# BespokeToast_Rev-0_v77.net
KiCad netlist of a schematic drawn in EAGLE
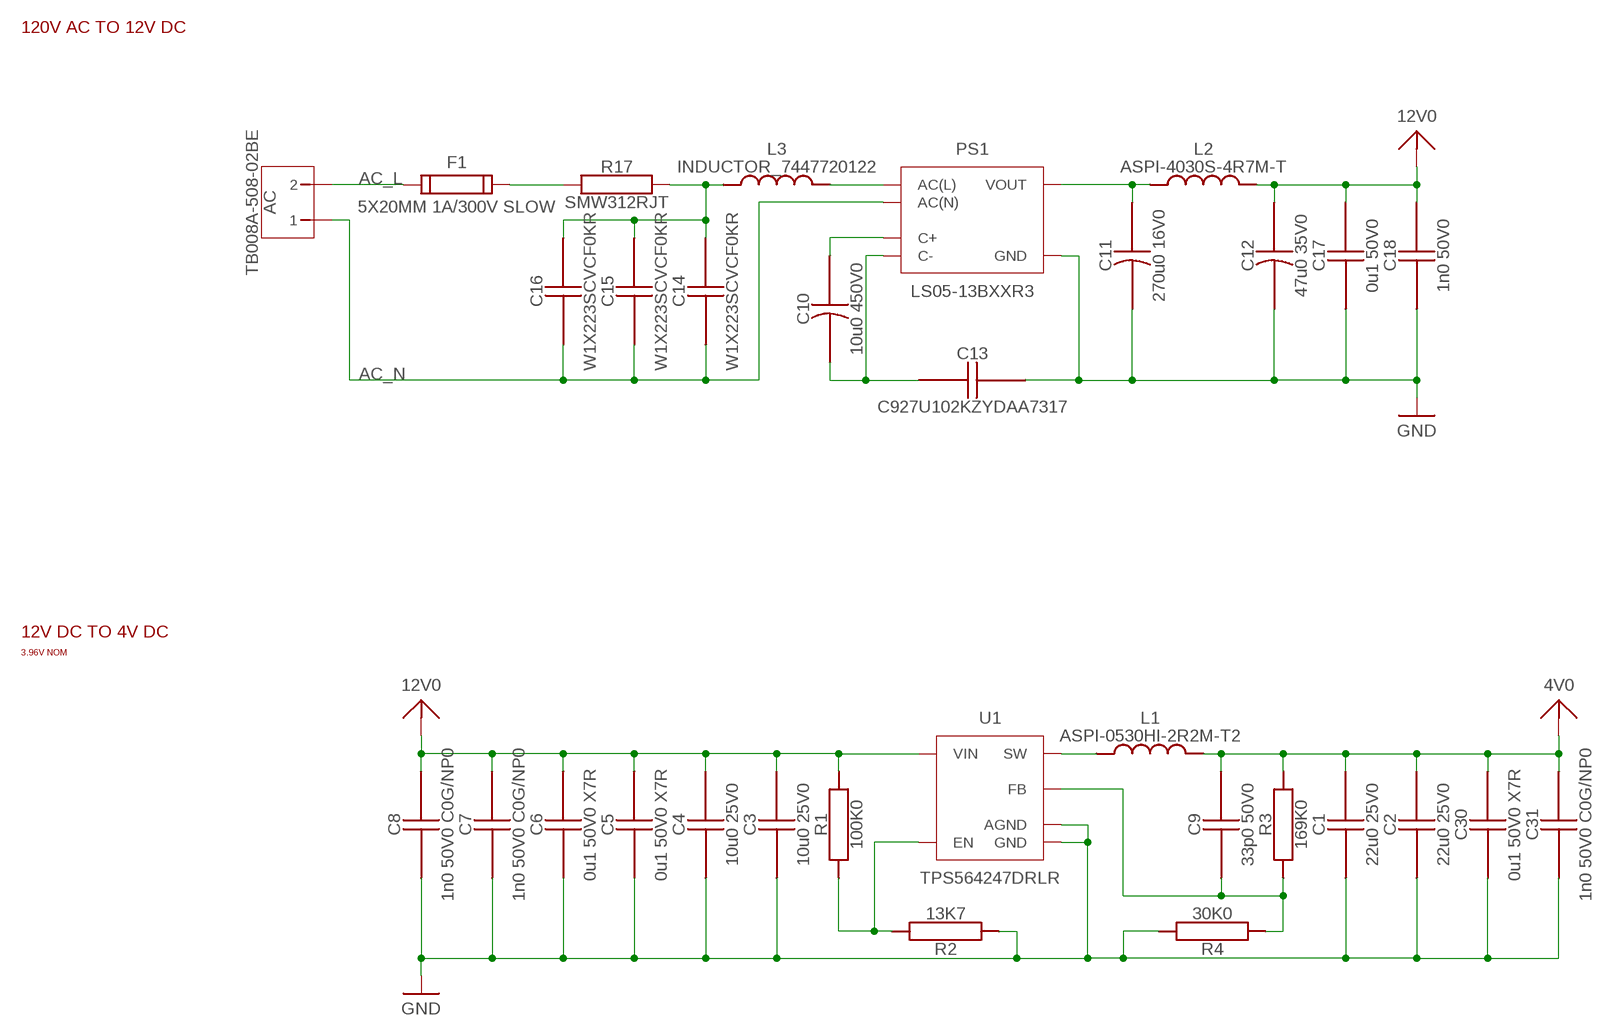
[diagram p0: schematic, sheet 1]
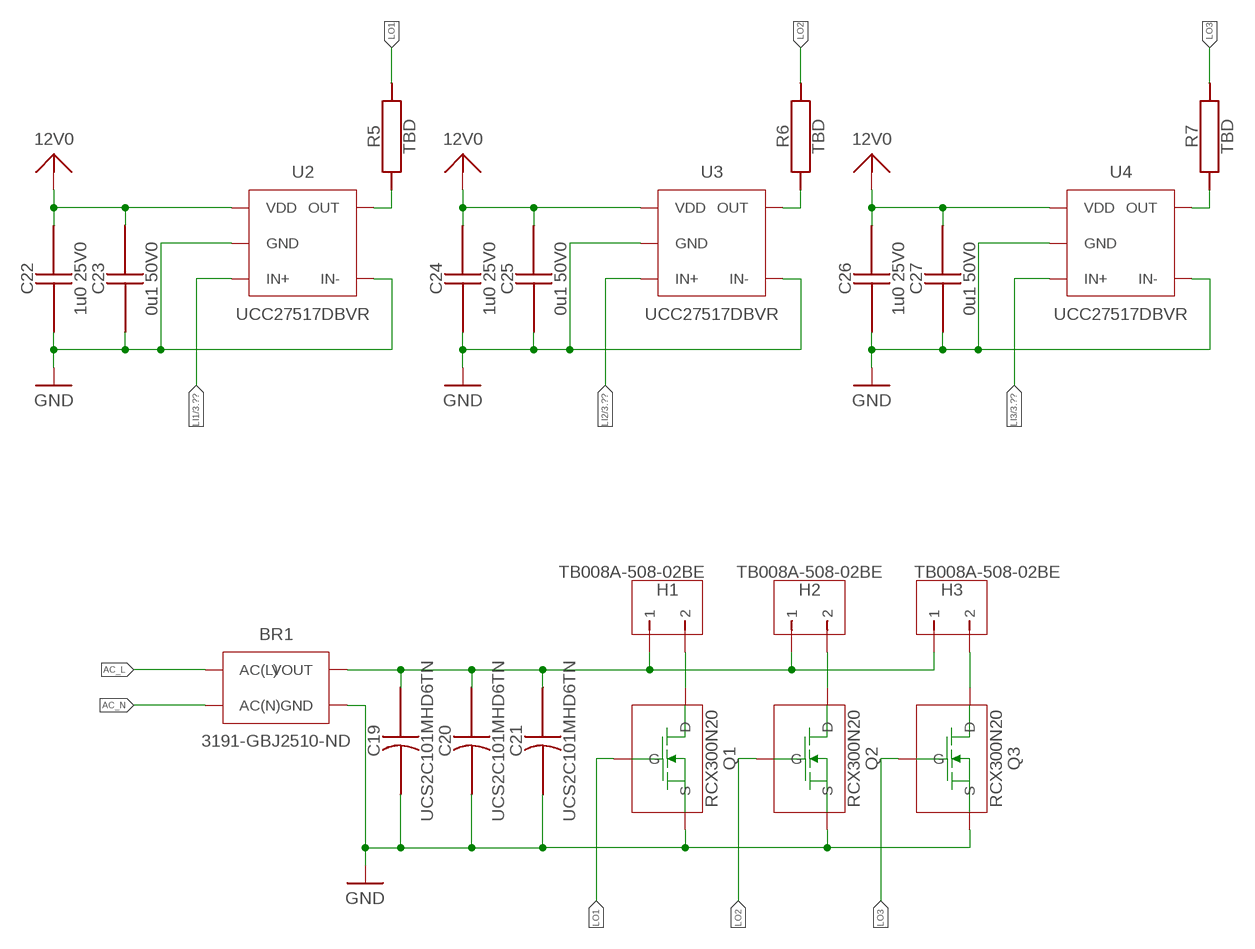
[diagram p1: schematic, sheet 2]
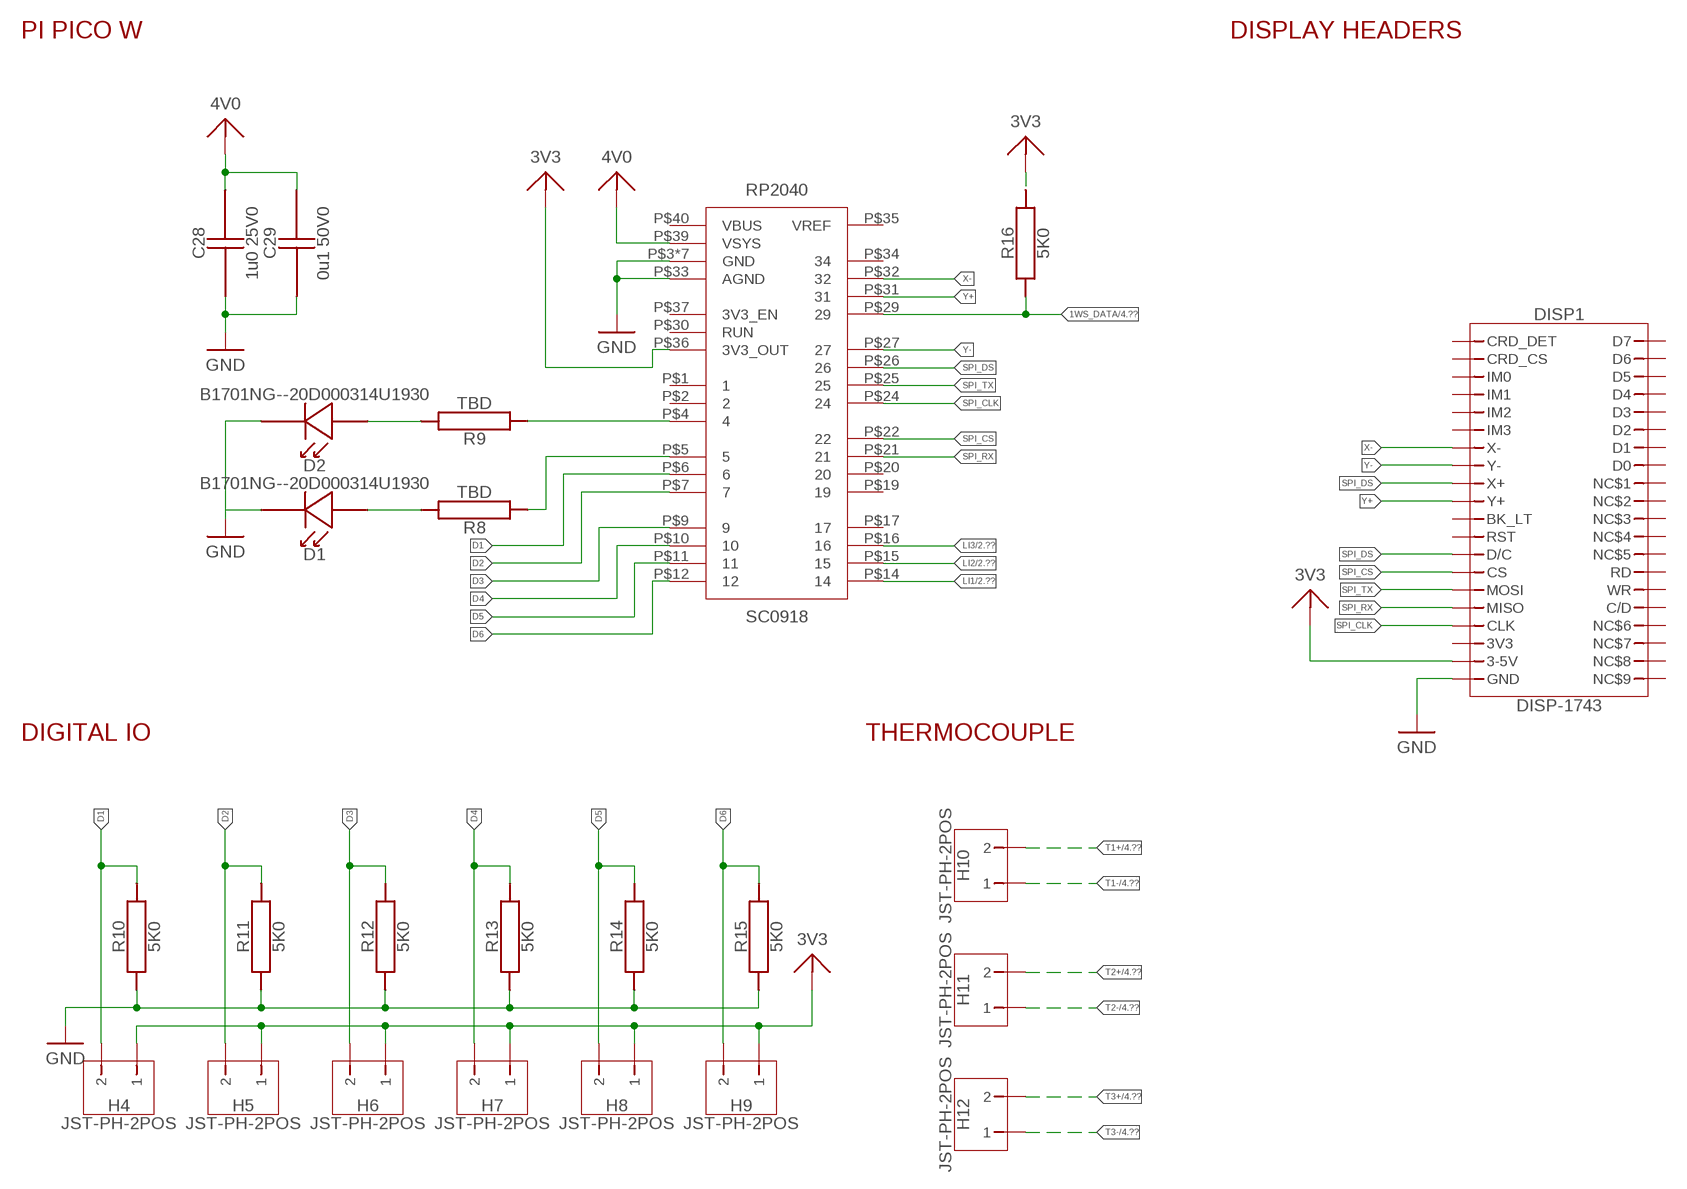
[diagram p2: schematic, sheet 3]
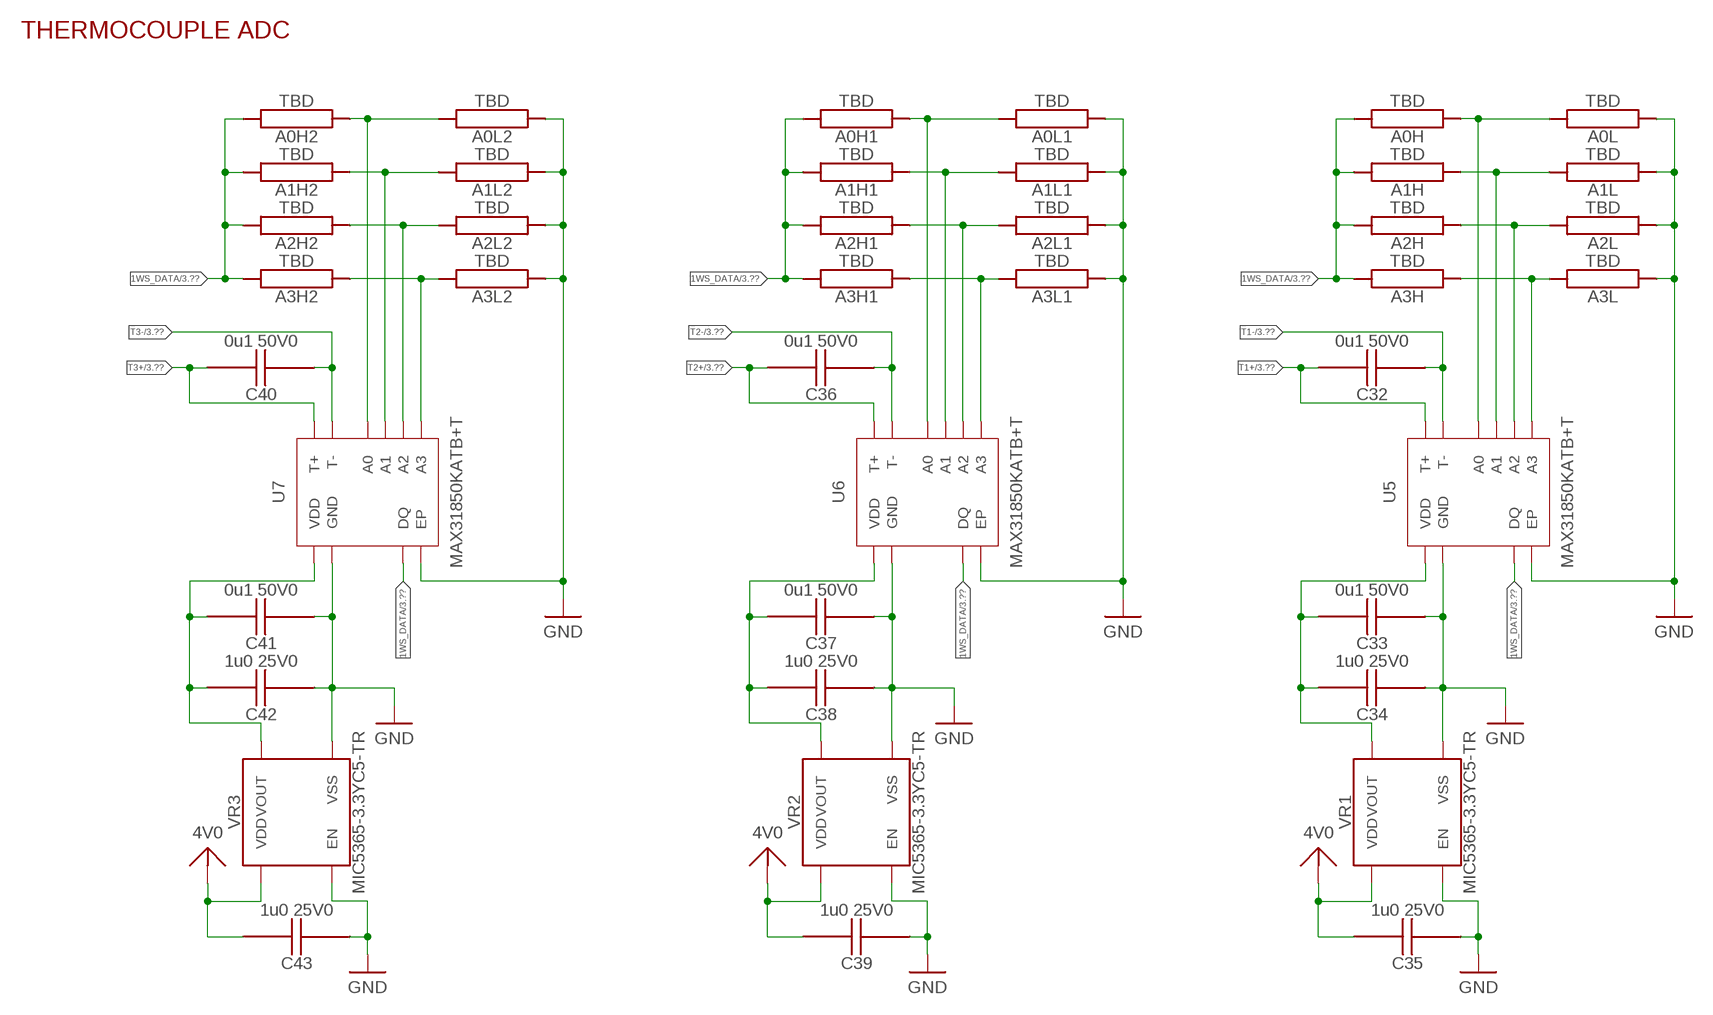
[diagram p3: schematic, sheet 4]

(export (version "E")
  (design (tool "Eeschema 10.0.6"))
  (components
    (comp (ref "BR1")
      (value "3191-GBJ2510-ND")
      (footprint "eagle-import:GBJ2510")
      (libsource (lib "eagle-import") (part "GBJ2510"))
    )
    (comp (ref "C19")
      (value "UCS2C101MHD6TN")
      (footprint "eagle-import:RUBYCON_CAP-POL-7.5X16")
      (libsource (lib "eagle-import") (part "CAP-POL_RUBYCON_CAP-POL-7.5X16"))
    )
    (comp (ref "C20")
      (value "UCS2C101MHD6TN")
      (footprint "eagle-import:RUBYCON_CAP-POL-7.5X16")
      (libsource (lib "eagle-import") (part "CAP-POL_RUBYCON_CAP-POL-7.5X16"))
    )
    (comp (ref "C21")
      (value "UCS2C101MHD6TN")
      (footprint "eagle-import:RUBYCON_CAP-POL-7.5X16")
      (libsource (lib "eagle-import") (part "CAP-POL_RUBYCON_CAP-POL-7.5X16"))
    )
    (comp (ref "C22")
      (value "1u0 25V0")
      (footprint "eagle-import:SAMSUNG_CAP-0805")
      (libsource (lib "eagle-import") (part "CAP-NON-POL_SAMSUNG-0805"))
    )
    (comp (ref "C23")
      (value "0u1 50V0")
      (footprint "eagle-import:SAMSUNG_CAP-0402")
      (libsource (lib "eagle-import") (part "CAP-NON-POL_SAMSUNG-0402"))
    )
    (comp (ref "C24")
      (value "1u0 25V0")
      (footprint "eagle-import:SAMSUNG_CAP-0805")
      (libsource (lib "eagle-import") (part "CAP-NON-POL_SAMSUNG-0805"))
    )
    (comp (ref "C25")
      (value "0u1 50V0")
      (footprint "eagle-import:SAMSUNG_CAP-0402")
      (libsource (lib "eagle-import") (part "CAP-NON-POL_SAMSUNG-0402"))
    )
    (comp (ref "C26")
      (value "1u0 25V0")
      (footprint "eagle-import:SAMSUNG_CAP-0805")
      (libsource (lib "eagle-import") (part "CAP-NON-POL_SAMSUNG-0805"))
    )
    (comp (ref "C27")
      (value "0u1 50V0")
      (footprint "eagle-import:SAMSUNG_CAP-0402")
      (libsource (lib "eagle-import") (part "CAP-NON-POL_SAMSUNG-0402"))
    )
    (comp (ref "H1")
      (value "TB008A-508-02BE")
      (footprint "eagle-import:TB008A-508-02BE")
      (libsource (lib "eagle-import") (part "TB008A-508-02BE"))
    )
    (comp (ref "H2")
      (value "TB008A-508-02BE")
      (footprint "eagle-import:TB008A-508-02BE")
      (libsource (lib "eagle-import") (part "TB008A-508-02BE"))
    )
    (comp (ref "H3")
      (value "TB008A-508-02BE")
      (footprint "eagle-import:TB008A-508-02BE")
      (libsource (lib "eagle-import") (part "TB008A-508-02BE"))
    )
    (comp (ref "Q1")
      (value "RCX300N20")
      (footprint "eagle-import:FET_TO220-VTH")
      (libsource (lib "eagle-import") (part "FET-NCH_FET_TO220-VTH"))
    )
    (comp (ref "Q2")
      (value "RCX300N20")
      (footprint "eagle-import:FET_TO220-VTH")
      (libsource (lib "eagle-import") (part "FET-NCH_FET_TO220-VTH"))
    )
    (comp (ref "Q3")
      (value "RCX300N20")
      (footprint "eagle-import:FET_TO220-VTH")
      (libsource (lib "eagle-import") (part "FET-NCH_FET_TO220-VTH"))
    )
    (comp (ref "R5")
      (value "TBD")
      (footprint "eagle-import:YAGEO_RES-0402")
      (libsource (lib "eagle-import") (part "RES-CHIP_YAGEO-0402"))
    )
    (comp (ref "R6")
      (value "TBD")
      (footprint "eagle-import:YAGEO_RES-0402")
      (libsource (lib "eagle-import") (part "RES-CHIP_YAGEO-0402"))
    )
    (comp (ref "R7")
      (value "TBD")
      (footprint "eagle-import:YAGEO_RES-0402")
      (libsource (lib "eagle-import") (part "RES-CHIP_YAGEO-0402"))
    )
    (comp (ref "U2")
      (value "UCC27517DBVR")
      (footprint "eagle-import:UCC27517DBVR")
      (libsource (lib "eagle-import") (part "UCC27517DBVR"))
    )
    (comp (ref "U3")
      (value "UCC27517DBVR")
      (footprint "eagle-import:UCC27517DBVR")
      (libsource (lib "eagle-import") (part "UCC27517DBVR"))
    )
    (comp (ref "U4")
      (value "UCC27517DBVR")
      (footprint "eagle-import:UCC27517DBVR")
      (libsource (lib "eagle-import") (part "UCC27517DBVR"))
    )
    (comp (ref "C28")
      (value "1u0 25V0")
      (footprint "eagle-import:SAMSUNG_CAP-0805")
      (libsource (lib "eagle-import") (part "CAP-NON-POL_SAMSUNG-0805"))
    )
    (comp (ref "C29")
      (value "0u1 50V0")
      (footprint "eagle-import:SAMSUNG_CAP-0402")
      (libsource (lib "eagle-import") (part "CAP-NON-POL_SAMSUNG-0402"))
    )
    (comp (ref "D1")
      (value "B1701NG--20D000314U1930")
      (footprint "eagle-import:B1701NG--20D000314U1930")
      (libsource (lib "eagle-import") (part "DIODE-LED_B1701NG--20D000314U1930"))
    )
    (comp (ref "D2")
      (value "B1701NG--20D000314U1930")
      (footprint "eagle-import:B1701NG--20D000314U1930")
      (libsource (lib "eagle-import") (part "DIODE-LED_B1701NG--20D000314U1930"))
    )
    (comp (ref "DISP1")
      (value "DISP-1743")
      (footprint "eagle-import:DISP-1743")
      (libsource (lib "eagle-import") (part "DISP-1743"))
    )
    (comp (ref "H4")
      (value "JST-PH-2POS")
      (footprint "eagle-import:JST-PH-2POS")
      (libsource (lib "eagle-import") (part "JST-PH-2POS"))
    )
    (comp (ref "H5")
      (value "JST-PH-2POS")
      (footprint "eagle-import:JST-PH-2POS")
      (libsource (lib "eagle-import") (part "JST-PH-2POS"))
    )
    (comp (ref "H6")
      (value "JST-PH-2POS")
      (footprint "eagle-import:JST-PH-2POS")
      (libsource (lib "eagle-import") (part "JST-PH-2POS"))
    )
    (comp (ref "H7")
      (value "JST-PH-2POS")
      (footprint "eagle-import:JST-PH-2POS")
      (libsource (lib "eagle-import") (part "JST-PH-2POS"))
    )
    (comp (ref "H8")
      (value "JST-PH-2POS")
      (footprint "eagle-import:JST-PH-2POS")
      (libsource (lib "eagle-import") (part "JST-PH-2POS"))
    )
    (comp (ref "H9")
      (value "JST-PH-2POS")
      (footprint "eagle-import:JST-PH-2POS")
      (libsource (lib "eagle-import") (part "JST-PH-2POS"))
    )
    (comp (ref "H10")
      (value "JST-PH-2POS")
      (footprint "eagle-import:JST-PH-2POS")
      (libsource (lib "eagle-import") (part "JST-PH-2POS"))
    )
    (comp (ref "H11")
      (value "JST-PH-2POS")
      (footprint "eagle-import:JST-PH-2POS")
      (libsource (lib "eagle-import") (part "JST-PH-2POS"))
    )
    (comp (ref "H12")
      (value "JST-PH-2POS")
      (footprint "eagle-import:JST-PH-2POS")
      (libsource (lib "eagle-import") (part "JST-PH-2POS"))
    )
    (comp (ref "R8")
      (value "TBD")
      (footprint "eagle-import:YAGEO_RES-0402")
      (libsource (lib "eagle-import") (part "RES-CHIP_YAGEO-0402"))
    )
    (comp (ref "R9")
      (value "TBD")
      (footprint "eagle-import:YAGEO_RES-0402")
      (libsource (lib "eagle-import") (part "RES-CHIP_YAGEO-0402"))
    )
    (comp (ref "R10")
      (value "5K0")
      (footprint "eagle-import:YAGEO_RES-0402")
      (libsource (lib "eagle-import") (part "RES-CHIP_YAGEO-0402"))
    )
    (comp (ref "R11")
      (value "5K0")
      (footprint "eagle-import:YAGEO_RES-0402")
      (libsource (lib "eagle-import") (part "RES-CHIP_YAGEO-0402"))
    )
    (comp (ref "R12")
      (value "5K0")
      (footprint "eagle-import:YAGEO_RES-0402")
      (libsource (lib "eagle-import") (part "RES-CHIP_YAGEO-0402"))
    )
    (comp (ref "R13")
      (value "5K0")
      (footprint "eagle-import:YAGEO_RES-0402")
      (libsource (lib "eagle-import") (part "RES-CHIP_YAGEO-0402"))
    )
    (comp (ref "R14")
      (value "5K0")
      (footprint "eagle-import:YAGEO_RES-0402")
      (libsource (lib "eagle-import") (part "RES-CHIP_YAGEO-0402"))
    )
    (comp (ref "R15")
      (value "5K0")
      (footprint "eagle-import:YAGEO_RES-0402")
      (libsource (lib "eagle-import") (part "RES-CHIP_YAGEO-0402"))
    )
    (comp (ref "R16")
      (value "5K0")
      (footprint "eagle-import:YAGEO_RES-0402")
      (libsource (lib "eagle-import") (part "RES-CHIP_YAGEO-0402"))
    )
    (comp (ref "RP2040")
      (value "SC0918")
      (footprint "eagle-import:SC0915")
      (libsource (lib "eagle-import") (part "SC0915"))
    )
    (comp (ref "A0H")
      (value "TBD")
      (footprint "eagle-import:YAGEO_RES-0402")
      (fields (field (name "SPICEPREFIX") "B"))
      (libsource (lib "eagle-import") (part "RES-CHIP_YAGEO-0402"))
    )
    (comp (ref "A0H1")
      (value "TBD")
      (footprint "eagle-import:YAGEO_RES-0402")
      (fields (field (name "SPICEPREFIX") "B"))
      (libsource (lib "eagle-import") (part "RES-CHIP_YAGEO-0402"))
    )
    (comp (ref "A0H2")
      (value "TBD")
      (footprint "eagle-import:YAGEO_RES-0402")
      (fields (field (name "SPICEPREFIX") "B"))
      (libsource (lib "eagle-import") (part "RES-CHIP_YAGEO-0402"))
    )
    (comp (ref "A0L")
      (value "TBD")
      (footprint "eagle-import:YAGEO_RES-0402")
      (fields (field (name "SPICEPREFIX") "B"))
      (libsource (lib "eagle-import") (part "RES-CHIP_YAGEO-0402"))
    )
    (comp (ref "A0L1")
      (value "TBD")
      (footprint "eagle-import:YAGEO_RES-0402")
      (fields (field (name "SPICEPREFIX") "B"))
      (libsource (lib "eagle-import") (part "RES-CHIP_YAGEO-0402"))
    )
    (comp (ref "A0L2")
      (value "TBD")
      (footprint "eagle-import:YAGEO_RES-0402")
      (fields (field (name "SPICEPREFIX") "B"))
      (libsource (lib "eagle-import") (part "RES-CHIP_YAGEO-0402"))
    )
    (comp (ref "A1H")
      (value "TBD")
      (footprint "eagle-import:YAGEO_RES-0402")
      (fields (field (name "SPICEPREFIX") "B"))
      (libsource (lib "eagle-import") (part "RES-CHIP_YAGEO-0402"))
    )
    (comp (ref "A1H1")
      (value "TBD")
      (footprint "eagle-import:YAGEO_RES-0402")
      (fields (field (name "SPICEPREFIX") "B"))
      (libsource (lib "eagle-import") (part "RES-CHIP_YAGEO-0402"))
    )
    (comp (ref "A1H2")
      (value "TBD")
      (footprint "eagle-import:YAGEO_RES-0402")
      (fields (field (name "SPICEPREFIX") "B"))
      (libsource (lib "eagle-import") (part "RES-CHIP_YAGEO-0402"))
    )
    (comp (ref "A1L")
      (value "TBD")
      (footprint "eagle-import:YAGEO_RES-0402")
      (fields (field (name "SPICEPREFIX") "B"))
      (libsource (lib "eagle-import") (part "RES-CHIP_YAGEO-0402"))
    )
    (comp (ref "A1L1")
      (value "TBD")
      (footprint "eagle-import:YAGEO_RES-0402")
      (fields (field (name "SPICEPREFIX") "B"))
      (libsource (lib "eagle-import") (part "RES-CHIP_YAGEO-0402"))
    )
    (comp (ref "A1L2")
      (value "TBD")
      (footprint "eagle-import:YAGEO_RES-0402")
      (fields (field (name "SPICEPREFIX") "B"))
      (libsource (lib "eagle-import") (part "RES-CHIP_YAGEO-0402"))
    )
    (comp (ref "A2H")
      (value "TBD")
      (footprint "eagle-import:YAGEO_RES-0402")
      (fields (field (name "SPICEPREFIX") "B"))
      (libsource (lib "eagle-import") (part "RES-CHIP_YAGEO-0402"))
    )
    (comp (ref "A2H1")
      (value "TBD")
      (footprint "eagle-import:YAGEO_RES-0402")
      (fields (field (name "SPICEPREFIX") "B"))
      (libsource (lib "eagle-import") (part "RES-CHIP_YAGEO-0402"))
    )
    (comp (ref "A2H2")
      (value "TBD")
      (footprint "eagle-import:YAGEO_RES-0402")
      (fields (field (name "SPICEPREFIX") "B"))
      (libsource (lib "eagle-import") (part "RES-CHIP_YAGEO-0402"))
    )
    (comp (ref "A2L")
      (value "TBD")
      (footprint "eagle-import:YAGEO_RES-0402")
      (fields (field (name "SPICEPREFIX") "B"))
      (libsource (lib "eagle-import") (part "RES-CHIP_YAGEO-0402"))
    )
    (comp (ref "A2L1")
      (value "TBD")
      (footprint "eagle-import:YAGEO_RES-0402")
      (fields (field (name "SPICEPREFIX") "B"))
      (libsource (lib "eagle-import") (part "RES-CHIP_YAGEO-0402"))
    )
    (comp (ref "A2L2")
      (value "TBD")
      (footprint "eagle-import:YAGEO_RES-0402")
      (fields (field (name "SPICEPREFIX") "B"))
      (libsource (lib "eagle-import") (part "RES-CHIP_YAGEO-0402"))
    )
    (comp (ref "A3H")
      (value "TBD")
      (footprint "eagle-import:YAGEO_RES-0402")
      (fields (field (name "SPICEPREFIX") "B"))
      (libsource (lib "eagle-import") (part "RES-CHIP_YAGEO-0402"))
    )
    (comp (ref "A3H1")
      (value "TBD")
      (footprint "eagle-import:YAGEO_RES-0402")
      (fields (field (name "SPICEPREFIX") "B"))
      (libsource (lib "eagle-import") (part "RES-CHIP_YAGEO-0402"))
    )
    (comp (ref "A3H2")
      (value "TBD")
      (footprint "eagle-import:YAGEO_RES-0402")
      (fields (field (name "SPICEPREFIX") "B"))
      (libsource (lib "eagle-import") (part "RES-CHIP_YAGEO-0402"))
    )
    (comp (ref "A3L")
      (value "TBD")
      (footprint "eagle-import:YAGEO_RES-0402")
      (fields (field (name "SPICEPREFIX") "B"))
      (libsource (lib "eagle-import") (part "RES-CHIP_YAGEO-0402"))
    )
    (comp (ref "A3L1")
      (value "TBD")
      (footprint "eagle-import:YAGEO_RES-0402")
      (fields (field (name "SPICEPREFIX") "B"))
      (libsource (lib "eagle-import") (part "RES-CHIP_YAGEO-0402"))
    )
    (comp (ref "A3L2")
      (value "TBD")
      (footprint "eagle-import:YAGEO_RES-0402")
      (fields (field (name "SPICEPREFIX") "B"))
      (libsource (lib "eagle-import") (part "RES-CHIP_YAGEO-0402"))
    )
    (comp (ref "C32")
      (value "0u1 50V0")
      (footprint "eagle-import:SAMSUNG_CAP-0402")
      (fields (field (name "SPICEPREFIX") "C"))
      (libsource (lib "eagle-import") (part "CAP-NON-POL_SAMSUNG-0402"))
    )
    (comp (ref "C33")
      (value "0u1 50V0")
      (footprint "eagle-import:SAMSUNG_CAP-0402")
      (fields (field (name "SPICEPREFIX") "C"))
      (libsource (lib "eagle-import") (part "CAP-NON-POL_SAMSUNG-0402"))
    )
    (comp (ref "C34")
      (value "1u0 25V0")
      (footprint "eagle-import:SAMSUNG_CAP-0603")
      (fields (field (name "SPICEPREFIX") "C"))
      (libsource (lib "eagle-import") (part "CAP-NON-POL_SAMSUNG-0603"))
    )
    (comp (ref "C35")
      (value "1u0 25V0")
      (footprint "eagle-import:SAMSUNG_CAP-0603")
      (fields (field (name "SPICEPREFIX") "C"))
      (libsource (lib "eagle-import") (part "CAP-NON-POL_SAMSUNG-0603"))
    )
    (comp (ref "C36")
      (value "0u1 50V0")
      (footprint "eagle-import:SAMSUNG_CAP-0402")
      (fields (field (name "SPICEPREFIX") "C"))
      (libsource (lib "eagle-import") (part "CAP-NON-POL_SAMSUNG-0402"))
    )
    (comp (ref "C37")
      (value "0u1 50V0")
      (footprint "eagle-import:SAMSUNG_CAP-0402")
      (fields (field (name "SPICEPREFIX") "C"))
      (libsource (lib "eagle-import") (part "CAP-NON-POL_SAMSUNG-0402"))
    )
    (comp (ref "C38")
      (value "1u0 25V0")
      (footprint "eagle-import:SAMSUNG_CAP-0603")
      (fields (field (name "SPICEPREFIX") "C"))
      (libsource (lib "eagle-import") (part "CAP-NON-POL_SAMSUNG-0603"))
    )
    (comp (ref "C39")
      (value "1u0 25V0")
      (footprint "eagle-import:SAMSUNG_CAP-0603")
      (fields (field (name "SPICEPREFIX") "C"))
      (libsource (lib "eagle-import") (part "CAP-NON-POL_SAMSUNG-0603"))
    )
    (comp (ref "C40")
      (value "0u1 50V0")
      (footprint "eagle-import:SAMSUNG_CAP-0402")
      (fields (field (name "SPICEPREFIX") "C"))
      (libsource (lib "eagle-import") (part "CAP-NON-POL_SAMSUNG-0402"))
    )
    (comp (ref "C41")
      (value "0u1 50V0")
      (footprint "eagle-import:SAMSUNG_CAP-0402")
      (fields (field (name "SPICEPREFIX") "C"))
      (libsource (lib "eagle-import") (part "CAP-NON-POL_SAMSUNG-0402"))
    )
    (comp (ref "C42")
      (value "1u0 25V0")
      (footprint "eagle-import:SAMSUNG_CAP-0603")
      (fields (field (name "SPICEPREFIX") "C"))
      (libsource (lib "eagle-import") (part "CAP-NON-POL_SAMSUNG-0603"))
    )
    (comp (ref "C43")
      (value "1u0 25V0")
      (footprint "eagle-import:SAMSUNG_CAP-0603")
      (fields (field (name "SPICEPREFIX") "C"))
      (libsource (lib "eagle-import") (part "CAP-NON-POL_SAMSUNG-0603"))
    )
    (comp (ref "U5")
      (value "MAX31850KATB+T")
      (footprint "eagle-import:MAX31850")
      (fields (field (name "SPICEPREFIX") "X"))
      (libsource (lib "eagle-import") (part "MAX31850_MAX31850KATB+T"))
    )
    (comp (ref "U6")
      (value "MAX31850KATB+T")
      (footprint "eagle-import:MAX31850")
      (fields (field (name "SPICEPREFIX") "X"))
      (libsource (lib "eagle-import") (part "MAX31850_MAX31850KATB+T"))
    )
    (comp (ref "U7")
      (value "MAX31850KATB+T")
      (footprint "eagle-import:MAX31850")
      (fields (field (name "SPICEPREFIX") "X"))
      (libsource (lib "eagle-import") (part "MAX31850_MAX31850KATB+T"))
    )
    (comp (ref "VR1")
      (value "MIC5365-3.3YC5-TR")
      (footprint "eagle-import:MIC5365-3.3YC5-TR")
      (fields (field (name "SPICEPREFIX") "E"))
      (libsource (lib "eagle-import") (part "MIC5365-3.3YC5-TR{dblquote}"))
    )
    (comp (ref "VR2")
      (value "MIC5365-3.3YC5-TR")
      (footprint "eagle-import:MIC5365-3.3YC5-TR")
      (fields (field (name "SPICEPREFIX") "E"))
      (libsource (lib "eagle-import") (part "MIC5365-3.3YC5-TR{dblquote}"))
    )
    (comp (ref "VR3")
      (value "MIC5365-3.3YC5-TR")
      (footprint "eagle-import:MIC5365-3.3YC5-TR")
      (fields (field (name "SPICEPREFIX") "E"))
      (libsource (lib "eagle-import") (part "MIC5365-3.3YC5-TR{dblquote}"))
    )
    (comp (ref "AC")
      (value "TB008A-508-02BE")
      (footprint "eagle-import:TB008A-508-02BE")
      (libsource (lib "eagle-import") (part "TB008A-508-02BE"))
    )
    (comp (ref "C1")
      (value "22u0 25V0")
      (footprint "eagle-import:SAMSUNG_CAP-0805")
      (libsource (lib "eagle-import") (part "CAP-NON-POL_SAMSUNG-0805"))
    )
    (comp (ref "C2")
      (value "22u0 25V0")
      (footprint "eagle-import:SAMSUNG_CAP-0805")
      (libsource (lib "eagle-import") (part "CAP-NON-POL_SAMSUNG-0805"))
    )
    (comp (ref "C3")
      (value "10u0 25V0")
      (footprint "eagle-import:SAMSUNG_CAP-0805")
      (libsource (lib "eagle-import") (part "CAP-NON-POL_SAMSUNG-0805"))
    )
    (comp (ref "C4")
      (value "10u0 25V0")
      (footprint "eagle-import:SAMSUNG_CAP-0805")
      (libsource (lib "eagle-import") (part "CAP-NON-POL_SAMSUNG-0805"))
    )
    (comp (ref "C5")
      (value "0u1 50V0 X7R")
      (footprint "eagle-import:SAMSUNG_CAP-0402")
      (libsource (lib "eagle-import") (part "CAP-NON-POL_SAMSUNG-0402"))
    )
    (comp (ref "C6")
      (value "0u1 50V0 X7R")
      (footprint "eagle-import:SAMSUNG_CAP-0402")
      (libsource (lib "eagle-import") (part "CAP-NON-POL_SAMSUNG-0402"))
    )
    (comp (ref "C7")
      (value "1n0 50V0 C0G/NP0")
      (footprint "eagle-import:SAMSUNG_CAP-0402")
      (libsource (lib "eagle-import") (part "CAP-NON-POL_SAMSUNG-0402"))
    )
    (comp (ref "C8")
      (value "1n0 50V0 C0G/NP0")
      (footprint "eagle-import:SAMSUNG_CAP-0402")
      (libsource (lib "eagle-import") (part "CAP-NON-POL_SAMSUNG-0402"))
    )
    (comp (ref "C9")
      (value "33p0 50V0")
      (footprint "eagle-import:SAMSUNG_CAP-0402")
      (libsource (lib "eagle-import") (part "CAP-NON-POL_SAMSUNG-0402"))
    )
    (comp (ref "C10")
      (value "10u0 450V0")
      (footprint "eagle-import:RUBYCON_CAP-POL-5X10")
      (libsource (lib "eagle-import") (part "CAP-POL_RUBYCON_CAP-POL-5X10"))
    )
    (comp (ref "C11")
      (value "270u0 16V0")
      (footprint "eagle-import:RUBYCON_CAP-POL-3.5X8")
      (libsource (lib "eagle-import") (part "CAP-POL_RUBYCON_CAP-POL-3.5X8"))
    )
    (comp (ref "C12")
      (value "47u0 35V0")
      (footprint "eagle-import:RUBYCON_CAP-POL-3.5X8")
      (libsource (lib "eagle-import") (part "CAP-POL_RUBYCON_CAP-POL-3.5X8"))
    )
    (comp (ref "C13")
      (value "C927U102KZYDAA7317")
      (footprint "eagle-import:TH_CAP-7.5")
      (libsource (lib "eagle-import") (part "CAP-NON-POL_TC_CAP-7.5"))
    )
    (comp (ref "C14")
      (value "W1X223SCVCF0KR")
      (footprint "eagle-import:TH_CAP-7.5")
      (libsource (lib "eagle-import") (part "CAP-NON-POL_TC_CAP-7.5"))
    )
    (comp (ref "C15")
      (value "W1X223SCVCF0KR")
      (footprint "eagle-import:TH_CAP-7.5")
      (libsource (lib "eagle-import") (part "CAP-NON-POL_TC_CAP-7.5"))
    )
    (comp (ref "C16")
      (value "W1X223SCVCF0KR")
      (footprint "eagle-import:TH_CAP-7.5")
      (libsource (lib "eagle-import") (part "CAP-NON-POL_TC_CAP-7.5"))
    )
    (comp (ref "C17")
      (value "0u1 50V0")
      (footprint "eagle-import:SAMSUNG_CAP-0402")
      (libsource (lib "eagle-import") (part "CAP-NON-POL_SAMSUNG-0402"))
    )
    (comp (ref "C18")
      (value "1n0 50V0")
      (footprint "eagle-import:SAMSUNG_CAP-0402")
      (libsource (lib "eagle-import") (part "CAP-NON-POL_SAMSUNG-0402"))
    )
    (comp (ref "C30")
      (value "0u1 50V0 X7R")
      (footprint "eagle-import:SAMSUNG_CAP-0402")
      (libsource (lib "eagle-import") (part "CAP-NON-POL_SAMSUNG-0402"))
    )
    (comp (ref "C31")
      (value "1n0 50V0 C0G/NP0")
      (footprint "eagle-import:SAMSUNG_CAP-0402")
      (libsource (lib "eagle-import") (part "CAP-NON-POL_SAMSUNG-0402"))
    )
    (comp (ref "F1")
      (value "5X20MM 1A/300V SLOW")
      (footprint "eagle-import:FC-203-22")
      (libsource (lib "eagle-import") (part "FUSE_FC-203-22-5X20MM"))
    )
    (comp (ref "L1")
      (value "ASPI-0530HI-2R2M-T2")
      (footprint "eagle-import:ASPI-0530HI-2R2M-T2")
      (libsource (lib "eagle-import") (part "INDUCTOR_ASPI-0530HI-2R2M-T2"))
    )
    (comp (ref "L2")
      (value "ASPI-4030S-4R7M-T")
      (footprint "eagle-import:ASPI-4030S-4R7M-T")
      (libsource (lib "eagle-import") (part "INDUCTOR_ASPI-4030S-4R7M-T"))
    )
    (comp (ref "L3")
      (value "INDUCTOR_7447720122")
      (footprint "eagle-import:7447720122")
      (libsource (lib "eagle-import") (part "INDUCTOR_7447720122"))
    )
    (comp (ref "PS1")
      (value "LS05-13BXXR3")
      (footprint "eagle-import:LS05-13BXXR3")
      (libsource (lib "eagle-import") (part "LS05-13BXXR3"))
    )
    (comp (ref "R1")
      (value "100K0")
      (footprint "eagle-import:YAGEO_RES-0402")
      (libsource (lib "eagle-import") (part "RES-CHIP_YAGEO-0402"))
    )
    (comp (ref "R2")
      (value "13K7")
      (footprint "eagle-import:YAGEO_RES-0402")
      (libsource (lib "eagle-import") (part "RES-CHIP_YAGEO-0402"))
    )
    (comp (ref "R3")
      (value "169K0")
      (footprint "eagle-import:YAGEO_RES-0402")
      (libsource (lib "eagle-import") (part "RES-CHIP_YAGEO-0402"))
    )
    (comp (ref "R4")
      (value "30K0")
      (footprint "eagle-import:YAGEO_RES-0402")
      (libsource (lib "eagle-import") (part "RES-CHIP_YAGEO-0402"))
    )
    (comp (ref "R17")
      (value "SMW312RJT")
      (footprint "eagle-import:SMW312RJT")
      (libsource (lib "eagle-import") (part "SMW312RJT"))
    )
    (comp (ref "U1")
      (value "TPS564247DRLR")
      (footprint "eagle-import:TPS564247DRLR")
      (libsource (lib "eagle-import") (part "TPS564247DRLR"))
    )
  )
  (nets
    (net (code "1") (name "1WS_DATA") (class "Default")
      (node (ref "A0H") (pin "P$2") (pinfunction "P$2_P$2") (pintype "bidirectional"))
      (node (ref "A0H1") (pin "P$2") (pinfunction "P$2_P$2") (pintype "bidirectional"))
      (node (ref "A0H2") (pin "P$2") (pinfunction "P$2_P$2") (pintype "bidirectional"))
      (node (ref "A1H") (pin "P$2") (pinfunction "P$2_P$2") (pintype "bidirectional"))
      (node (ref "A1H1") (pin "P$2") (pinfunction "P$2_P$2") (pintype "bidirectional"))
      (node (ref "A1H2") (pin "P$2") (pinfunction "P$2_P$2") (pintype "bidirectional"))
      (node (ref "A2H") (pin "P$2") (pinfunction "P$2_P$2") (pintype "bidirectional"))
      (node (ref "A2H1") (pin "P$2") (pinfunction "P$2_P$2") (pintype "bidirectional"))
      (node (ref "A2H2") (pin "P$2") (pinfunction "P$2_P$2") (pintype "bidirectional"))
      (node (ref "A3H") (pin "P$2") (pinfunction "P$2_P$2") (pintype "bidirectional"))
      (node (ref "A3H1") (pin "P$2") (pinfunction "P$2_P$2") (pintype "bidirectional"))
      (node (ref "A3H2") (pin "P$2") (pinfunction "P$2_P$2") (pintype "bidirectional"))
      (node (ref "R16") (pin "P$1") (pinfunction "P$1_P$1") (pintype "bidirectional"))
      (node (ref "RP2040") (pin "P$29") (pinfunction "29_P$29") (pintype "bidirectional"))
      (node (ref "U5") (pin "P$5") (pinfunction "DQ_P$5") (pintype "bidirectional"))
      (node (ref "U6") (pin "P$5") (pinfunction "DQ_P$5") (pintype "bidirectional"))
      (node (ref "U7") (pin "P$5") (pinfunction "DQ_P$5") (pintype "bidirectional"))
    )
    (net (code "2") (name "3V3") (class "Default")
      (node (ref "DISP1") (pin "P$19") (pinfunction "3-5V_P$19") (pintype "bidirectional"))
      (node (ref "H4") (pin "P$1") (pinfunction "1_P$1") (pintype "bidirectional"))
      (node (ref "H5") (pin "P$1") (pinfunction "1_P$1") (pintype "bidirectional"))
      (node (ref "H6") (pin "P$1") (pinfunction "1_P$1") (pintype "bidirectional"))
      (node (ref "H7") (pin "P$1") (pinfunction "1_P$1") (pintype "bidirectional"))
      (node (ref "H8") (pin "P$1") (pinfunction "1_P$1") (pintype "bidirectional"))
      (node (ref "H9") (pin "P$1") (pinfunction "1_P$1") (pintype "bidirectional"))
      (node (ref "R16") (pin "P$2") (pinfunction "P$2_P$2") (pintype "bidirectional"))
      (node (ref "RP2040") (pin "P$36") (pinfunction "3V3_OUT_P$36") (pintype "bidirectional"))
    )
    (net (code "3") (name "4V0") (class "Default")
      (node (ref "C1") (pin "P$2") (pinfunction "P$2_P$2") (pintype "bidirectional"))
      (node (ref "C2") (pin "P$2") (pinfunction "P$2_P$2") (pintype "bidirectional"))
      (node (ref "C28") (pin "P$2") (pinfunction "P$2_P$2") (pintype "bidirectional"))
      (node (ref "C29") (pin "P$2") (pinfunction "P$2_P$2") (pintype "bidirectional"))
      (node (ref "C30") (pin "P$2") (pinfunction "P$2_P$2") (pintype "bidirectional"))
      (node (ref "C31") (pin "P$2") (pinfunction "P$2_P$2") (pintype "bidirectional"))
      (node (ref "C35") (pin "P$2") (pinfunction "P$2_P$2") (pintype "bidirectional"))
      (node (ref "C39") (pin "P$2") (pinfunction "P$2_P$2") (pintype "bidirectional"))
      (node (ref "C43") (pin "P$2") (pinfunction "P$2_P$2") (pintype "bidirectional"))
      (node (ref "C9") (pin "P$2") (pinfunction "P$2_P$2") (pintype "bidirectional"))
      (node (ref "L1") (pin "P$2") (pinfunction "P$2_P$2") (pintype "bidirectional"))
      (node (ref "R3") (pin "P$2") (pinfunction "P$2_P$2") (pintype "bidirectional"))
      (node (ref "RP2040") (pin "P$39") (pinfunction "VSYS_P$39") (pintype "bidirectional"))
      (node (ref "VR1") (pin "P$1") (pinfunction "VDD_P$1") (pintype "bidirectional"))
      (node (ref "VR2") (pin "P$1") (pinfunction "VDD_P$1") (pintype "bidirectional"))
      (node (ref "VR3") (pin "P$1") (pinfunction "VDD_P$1") (pintype "bidirectional"))
    )
    (net (code "4") (name "12V0") (class "Default")
      (node (ref "C12") (pin "+") (pinfunction "+_+") (pintype "bidirectional"))
      (node (ref "C17") (pin "P$2") (pinfunction "P$2_P$2") (pintype "bidirectional"))
      (node (ref "C18") (pin "P$2") (pinfunction "P$2_P$2") (pintype "bidirectional"))
      (node (ref "C22") (pin "P$2") (pinfunction "P$2_P$2") (pintype "bidirectional"))
      (node (ref "C23") (pin "P$2") (pinfunction "P$2_P$2") (pintype "bidirectional"))
      (node (ref "C24") (pin "P$2") (pinfunction "P$2_P$2") (pintype "bidirectional"))
      (node (ref "C25") (pin "P$2") (pinfunction "P$2_P$2") (pintype "bidirectional"))
      (node (ref "C26") (pin "P$2") (pinfunction "P$2_P$2") (pintype "bidirectional"))
      (node (ref "C27") (pin "P$2") (pinfunction "P$2_P$2") (pintype "bidirectional"))
      (node (ref "C3") (pin "P$2") (pinfunction "P$2_P$2") (pintype "bidirectional"))
      (node (ref "C4") (pin "P$2") (pinfunction "P$2_P$2") (pintype "bidirectional"))
      (node (ref "C5") (pin "P$2") (pinfunction "P$2_P$2") (pintype "bidirectional"))
      (node (ref "C6") (pin "P$2") (pinfunction "P$2_P$2") (pintype "bidirectional"))
      (node (ref "C7") (pin "P$2") (pinfunction "P$2_P$2") (pintype "bidirectional"))
      (node (ref "C8") (pin "P$2") (pinfunction "P$2_P$2") (pintype "bidirectional"))
      (node (ref "L2") (pin "P$2") (pinfunction "P$2_P$2") (pintype "bidirectional"))
      (node (ref "R1") (pin "P$2") (pinfunction "P$2_P$2") (pintype "bidirectional"))
      (node (ref "U1") (pin "P$1") (pinfunction "VIN_P$1") (pintype "bidirectional"))
      (node (ref "U2") (pin "P$1") (pinfunction "VDD_P$1") (pintype "bidirectional"))
      (node (ref "U3") (pin "P$1") (pinfunction "VDD_P$1") (pintype "bidirectional"))
      (node (ref "U4") (pin "P$1") (pinfunction "VDD_P$1") (pintype "bidirectional"))
    )
    (net (code "5") (name "AC_L") (class "Default")
      (node (ref "AC") (pin "P$2") (pinfunction "2_P$2") (pintype "bidirectional"))
      (node (ref "BR1") (pin "P$2") (pinfunction "AC(L)_P$2") (pintype "bidirectional"))
      (node (ref "F1") (pin "P$1") (pinfunction "P$1_P$1") (pintype "bidirectional"))
      (node (ref "F1") (pin "P$2") (pinfunction "P$1_P$2") (pintype "bidirectional"))
    )
    (net (code "6") (name "AC_N") (class "Default")
      (node (ref "AC") (pin "P$1") (pinfunction "1_P$1") (pintype "bidirectional"))
      (node (ref "BR1") (pin "P$3") (pinfunction "AC(N)_P$3") (pintype "bidirectional"))
      (node (ref "C14") (pin "P$1") (pinfunction "P$1_P$1") (pintype "bidirectional"))
      (node (ref "C15") (pin "P$1") (pinfunction "P$1_P$1") (pintype "bidirectional"))
      (node (ref "C16") (pin "P$1") (pinfunction "P$1_P$1") (pintype "bidirectional"))
      (node (ref "PS1") (pin "P$2") (pinfunction "AC(N)_P$2") (pintype "bidirectional"))
    )
    (net (code "7") (name "D1") (class "Default")
      (node (ref "H4") (pin "P$2") (pinfunction "2_P$2") (pintype "bidirectional"))
      (node (ref "R10") (pin "P$2") (pinfunction "P$2_P$2") (pintype "bidirectional"))
      (node (ref "RP2040") (pin "P$6") (pinfunction "6_P$6") (pintype "bidirectional"))
    )
    (net (code "8") (name "D2") (class "Default")
      (node (ref "H5") (pin "P$2") (pinfunction "2_P$2") (pintype "bidirectional"))
      (node (ref "R11") (pin "P$2") (pinfunction "P$2_P$2") (pintype "bidirectional"))
      (node (ref "RP2040") (pin "P$7") (pinfunction "7_P$7") (pintype "bidirectional"))
    )
    (net (code "9") (name "D3") (class "Default")
      (node (ref "H6") (pin "P$2") (pinfunction "2_P$2") (pintype "bidirectional"))
      (node (ref "R12") (pin "P$2") (pinfunction "P$2_P$2") (pintype "bidirectional"))
      (node (ref "RP2040") (pin "P$9") (pinfunction "9_P$9") (pintype "bidirectional"))
    )
    (net (code "10") (name "D4") (class "Default")
      (node (ref "H7") (pin "P$2") (pinfunction "2_P$2") (pintype "bidirectional"))
      (node (ref "R13") (pin "P$2") (pinfunction "P$2_P$2") (pintype "bidirectional"))
      (node (ref "RP2040") (pin "P$10") (pinfunction "10_P$10") (pintype "bidirectional"))
    )
    (net (code "11") (name "D5") (class "Default")
      (node (ref "H8") (pin "P$2") (pinfunction "2_P$2") (pintype "bidirectional"))
      (node (ref "R14") (pin "P$2") (pinfunction "P$2_P$2") (pintype "bidirectional"))
      (node (ref "RP2040") (pin "P$11") (pinfunction "11_P$11") (pintype "bidirectional"))
    )
    (net (code "12") (name "D6") (class "Default")
      (node (ref "H9") (pin "P$2") (pinfunction "2_P$2") (pintype "bidirectional"))
      (node (ref "R15") (pin "P$2") (pinfunction "P$2_P$2") (pintype "bidirectional"))
      (node (ref "RP2040") (pin "P$12") (pinfunction "12_P$12") (pintype "bidirectional"))
    )
    (net (code "13") (name "GND") (class "Default")
      (node (ref "A0L") (pin "P$1") (pinfunction "P$1_P$1") (pintype "bidirectional"))
      (node (ref "A0L1") (pin "P$1") (pinfunction "P$1_P$1") (pintype "bidirectional"))
      (node (ref "A0L2") (pin "P$1") (pinfunction "P$1_P$1") (pintype "bidirectional"))
      (node (ref "A1L") (pin "P$1") (pinfunction "P$1_P$1") (pintype "bidirectional"))
      (node (ref "A1L1") (pin "P$1") (pinfunction "P$1_P$1") (pintype "bidirectional"))
      (node (ref "A1L2") (pin "P$1") (pinfunction "P$1_P$1") (pintype "bidirectional"))
      (node (ref "A2L") (pin "P$1") (pinfunction "P$1_P$1") (pintype "bidirectional"))
      (node (ref "A2L1") (pin "P$1") (pinfunction "P$1_P$1") (pintype "bidirectional"))
      (node (ref "A2L2") (pin "P$1") (pinfunction "P$1_P$1") (pintype "bidirectional"))
      (node (ref "A3L") (pin "P$1") (pinfunction "P$1_P$1") (pintype "bidirectional"))
      (node (ref "A3L1") (pin "P$1") (pinfunction "P$1_P$1") (pintype "bidirectional"))
      (node (ref "A3L2") (pin "P$1") (pinfunction "P$1_P$1") (pintype "bidirectional"))
      (node (ref "BR1") (pin "P$4") (pinfunction "GND_P$4") (pintype "bidirectional"))
      (node (ref "C1") (pin "P$1") (pinfunction "P$1_P$1") (pintype "bidirectional"))
      (node (ref "C11") (pin "-") (pinfunction "-_-") (pintype "bidirectional"))
      (node (ref "C12") (pin "-") (pinfunction "-_-") (pintype "bidirectional"))
      (node (ref "C13") (pin "P$2") (pinfunction "P$2_P$2") (pintype "bidirectional"))
      (node (ref "C17") (pin "P$1") (pinfunction "P$1_P$1") (pintype "bidirectional"))
      (node (ref "C18") (pin "P$1") (pinfunction "P$1_P$1") (pintype "bidirectional"))
      (node (ref "C19") (pin "-") (pinfunction "-_-") (pintype "bidirectional"))
      (node (ref "C2") (pin "P$1") (pinfunction "P$1_P$1") (pintype "bidirectional"))
      (node (ref "C20") (pin "-") (pinfunction "-_-") (pintype "bidirectional"))
      (node (ref "C21") (pin "-") (pinfunction "-_-") (pintype "bidirectional"))
      (node (ref "C22") (pin "P$1") (pinfunction "P$1_P$1") (pintype "bidirectional"))
      (node (ref "C23") (pin "P$1") (pinfunction "P$1_P$1") (pintype "bidirectional"))
      (node (ref "C24") (pin "P$1") (pinfunction "P$1_P$1") (pintype "bidirectional"))
      (node (ref "C25") (pin "P$1") (pinfunction "P$1_P$1") (pintype "bidirectional"))
      (node (ref "C26") (pin "P$1") (pinfunction "P$1_P$1") (pintype "bidirectional"))
      (node (ref "C27") (pin "P$1") (pinfunction "P$1_P$1") (pintype "bidirectional"))
      (node (ref "C28") (pin "P$1") (pinfunction "P$1_P$1") (pintype "bidirectional"))
      (node (ref "C29") (pin "P$1") (pinfunction "P$1_P$1") (pintype "bidirectional"))
      (node (ref "C3") (pin "P$1") (pinfunction "P$1_P$1") (pintype "bidirectional"))
      (node (ref "C30") (pin "P$1") (pinfunction "P$1_P$1") (pintype "bidirectional"))
      (node (ref "C31") (pin "P$1") (pinfunction "P$1_P$1") (pintype "bidirectional"))
      (node (ref "C33") (pin "P$1") (pinfunction "P$1_P$1") (pintype "bidirectional"))
      (node (ref "C34") (pin "P$1") (pinfunction "P$1_P$1") (pintype "bidirectional"))
      (node (ref "C35") (pin "P$1") (pinfunction "P$1_P$1") (pintype "bidirectional"))
      (node (ref "C37") (pin "P$1") (pinfunction "P$1_P$1") (pintype "bidirectional"))
      (node (ref "C38") (pin "P$1") (pinfunction "P$1_P$1") (pintype "bidirectional"))
      (node (ref "C39") (pin "P$1") (pinfunction "P$1_P$1") (pintype "bidirectional"))
      (node (ref "C4") (pin "P$1") (pinfunction "P$1_P$1") (pintype "bidirectional"))
      (node (ref "C41") (pin "P$1") (pinfunction "P$1_P$1") (pintype "bidirectional"))
      (node (ref "C42") (pin "P$1") (pinfunction "P$1_P$1") (pintype "bidirectional"))
      (node (ref "C43") (pin "P$1") (pinfunction "P$1_P$1") (pintype "bidirectional"))
      (node (ref "C5") (pin "P$1") (pinfunction "P$1_P$1") (pintype "bidirectional"))
      (node (ref "C6") (pin "P$1") (pinfunction "P$1_P$1") (pintype "bidirectional"))
      (node (ref "C7") (pin "P$1") (pinfunction "P$1_P$1") (pintype "bidirectional"))
      (node (ref "C8") (pin "P$1") (pinfunction "P$1_P$1") (pintype "bidirectional"))
      (node (ref "D1") (pin "P$1") (pinfunction "VSS_P$1") (pintype "bidirectional"))
      (node (ref "D2") (pin "P$1") (pinfunction "VSS_P$1") (pintype "bidirectional"))
      (node (ref "DISP1") (pin "P$20") (pinfunction "GND_P$20") (pintype "bidirectional"))
      (node (ref "PS1") (pin "P$5") (pinfunction "GND_P$5") (pintype "bidirectional"))
      (node (ref "Q1") (pin "S") (pinfunction "S_S") (pintype "bidirectional"))
      (node (ref "Q2") (pin "S") (pinfunction "S_S") (pintype "bidirectional"))
      (node (ref "Q3") (pin "S") (pinfunction "S_S") (pintype "bidirectional"))
      (node (ref "R10") (pin "P$1") (pinfunction "P$1_P$1") (pintype "bidirectional"))
      (node (ref "R11") (pin "P$1") (pinfunction "P$1_P$1") (pintype "bidirectional"))
      (node (ref "R12") (pin "P$1") (pinfunction "P$1_P$1") (pintype "bidirectional"))
      (node (ref "R13") (pin "P$1") (pinfunction "P$1_P$1") (pintype "bidirectional"))
      (node (ref "R14") (pin "P$1") (pinfunction "P$1_P$1") (pintype "bidirectional"))
      (node (ref "R15") (pin "P$1") (pinfunction "P$1_P$1") (pintype "bidirectional"))
      (node (ref "R2") (pin "P$1") (pinfunction "P$1_P$1") (pintype "bidirectional"))
      (node (ref "R4") (pin "P$2") (pinfunction "P$2_P$2") (pintype "bidirectional"))
      (node (ref "RP2040") (pin "P$13") (pinfunction "GND_P$13") (pintype "bidirectional"))
      (node (ref "RP2040") (pin "P$18") (pinfunction "GND_P$18") (pintype "bidirectional"))
      (node (ref "RP2040") (pin "P$23") (pinfunction "GND_P$23") (pintype "bidirectional"))
      (node (ref "RP2040") (pin "P$28") (pinfunction "GND_P$28") (pintype "bidirectional"))
      (node (ref "RP2040") (pin "P$3") (pinfunction "GND_P$3") (pintype "bidirectional"))
      (node (ref "RP2040") (pin "P$33") (pinfunction "AGND_P$33") (pintype "bidirectional"))
      (node (ref "RP2040") (pin "P$38") (pinfunction "GND_P$38") (pintype "bidirectional"))
      (node (ref "RP2040") (pin "P$8") (pinfunction "GND_P$8") (pintype "bidirectional"))
      (node (ref "U1") (pin "P$3") (pinfunction "GND_P$3") (pintype "bidirectional"))
      (node (ref "U1") (pin "P$4") (pinfunction "AGND_P$4") (pintype "bidirectional"))
      (node (ref "U2") (pin "P$2") (pinfunction "GND_P$2") (pintype "bidirectional"))
      (node (ref "U2") (pin "P$4") (pinfunction "IN-_P$4") (pintype "bidirectional"))
      (node (ref "U3") (pin "P$2") (pinfunction "GND_P$2") (pintype "bidirectional"))
      (node (ref "U3") (pin "P$4") (pinfunction "IN-_P$4") (pintype "bidirectional"))
      (node (ref "U4") (pin "P$2") (pinfunction "GND_P$2") (pintype "bidirectional"))
      (node (ref "U4") (pin "P$4") (pinfunction "IN-_P$4") (pintype "bidirectional"))
      (node (ref "U5") (pin "EP") (pinfunction "EP_EP") (pintype "bidirectional"))
      (node (ref "U5") (pin "P$1") (pinfunction "GND_P$1") (pintype "bidirectional"))
      (node (ref "U6") (pin "EP") (pinfunction "EP_EP") (pintype "bidirectional"))
      (node (ref "U6") (pin "P$1") (pinfunction "GND_P$1") (pintype "bidirectional"))
      (node (ref "U7") (pin "EP") (pinfunction "EP_EP") (pintype "bidirectional"))
      (node (ref "U7") (pin "P$1") (pinfunction "GND_P$1") (pintype "bidirectional"))
      (node (ref "VR1") (pin "P$2") (pinfunction "VSS_P$2") (pintype "bidirectional"))
      (node (ref "VR1") (pin "P$3") (pinfunction "EN_P$3") (pintype "bidirectional"))
      (node (ref "VR2") (pin "P$2") (pinfunction "VSS_P$2") (pintype "bidirectional"))
      (node (ref "VR2") (pin "P$3") (pinfunction "EN_P$3") (pintype "bidirectional"))
      (node (ref "VR3") (pin "P$2") (pinfunction "VSS_P$2") (pintype "bidirectional"))
      (node (ref "VR3") (pin "P$3") (pinfunction "EN_P$3") (pintype "bidirectional"))
    )
    (net (code "14") (name "LI1") (class "Default")
      (node (ref "RP2040") (pin "P$14") (pinfunction "14_P$14") (pintype "bidirectional"))
      (node (ref "U2") (pin "P$3") (pinfunction "IN+_P$3") (pintype "bidirectional"))
    )
    (net (code "15") (name "LI2") (class "Default")
      (node (ref "RP2040") (pin "P$15") (pinfunction "15_P$15") (pintype "bidirectional"))
      (node (ref "U3") (pin "P$3") (pinfunction "IN+_P$3") (pintype "bidirectional"))
    )
    (net (code "16") (name "LI3") (class "Default")
      (node (ref "RP2040") (pin "P$16") (pinfunction "16_P$16") (pintype "bidirectional"))
      (node (ref "U4") (pin "P$3") (pinfunction "IN+_P$3") (pintype "bidirectional"))
    )
    (net (code "17") (name "LO1") (class "Default")
      (node (ref "Q1") (pin "G") (pinfunction "G_G") (pintype "bidirectional"))
      (node (ref "R5") (pin "P$2") (pinfunction "P$2_P$2") (pintype "bidirectional"))
    )
    (net (code "18") (name "LO2") (class "Default")
      (node (ref "Q2") (pin "G") (pinfunction "G_G") (pintype "bidirectional"))
      (node (ref "R6") (pin "P$2") (pinfunction "P$2_P$2") (pintype "bidirectional"))
    )
    (net (code "19") (name "LO3") (class "Default")
      (node (ref "Q3") (pin "G") (pinfunction "G_G") (pintype "bidirectional"))
      (node (ref "R7") (pin "P$2") (pinfunction "P$2_P$2") (pintype "bidirectional"))
    )
    (net (code "20") (name "Net-(BR1-VOUT)") (class "Default")
      (node (ref "BR1") (pin "P$1") (pinfunction "VOUT_P$1") (pintype "bidirectional"))
      (node (ref "C19") (pin "+") (pinfunction "+_+") (pintype "bidirectional"))
      (node (ref "C20") (pin "+") (pinfunction "+_+") (pintype "bidirectional"))
      (node (ref "C21") (pin "+") (pinfunction "+_+") (pintype "bidirectional"))
      (node (ref "H1") (pin "P$1") (pinfunction "1_P$1") (pintype "bidirectional"))
      (node (ref "H2") (pin "P$1") (pinfunction "1_P$1") (pintype "bidirectional"))
      (node (ref "H3") (pin "P$1") (pinfunction "1_P$1") (pintype "bidirectional"))
    )
    (net (code "21") (name "Net-(D1-VDD)") (class "Default")
      (node (ref "D1") (pin "P$2") (pinfunction "VDD_P$2") (pintype "bidirectional"))
      (node (ref "R8") (pin "P$2") (pinfunction "P$2_P$2") (pintype "bidirectional"))
    )
    (net (code "22") (name "Net-(D2-VDD)") (class "Default")
      (node (ref "D2") (pin "P$2") (pinfunction "VDD_P$2") (pintype "bidirectional"))
      (node (ref "R9") (pin "P$2") (pinfunction "P$2_P$2") (pintype "bidirectional"))
    )
    (net (code "23") (name "Net-(H1-2)") (class "Default")
      (node (ref "H1") (pin "P$2") (pinfunction "2_P$2") (pintype "bidirectional"))
      (node (ref "Q1") (pin "D") (pinfunction "D_D") (pintype "bidirectional"))
    )
    (net (code "24") (name "Net-(H2-2)") (class "Default")
      (node (ref "H2") (pin "P$2") (pinfunction "2_P$2") (pintype "bidirectional"))
      (node (ref "Q2") (pin "D") (pinfunction "D_D") (pintype "bidirectional"))
    )
    (net (code "25") (name "Net-(H3-2)") (class "Default")
      (node (ref "H3") (pin "P$2") (pinfunction "2_P$2") (pintype "bidirectional"))
      (node (ref "Q3") (pin "D") (pinfunction "D_D") (pintype "bidirectional"))
    )
    (net (code "26") (name "Net-(PS1-AC(L))") (class "Default")
      (node (ref "L3") (pin "P$2") (pinfunction "P$2_P$2") (pintype "bidirectional"))
      (node (ref "PS1") (pin "P$1") (pinfunction "AC(L)_P$1") (pintype "bidirectional"))
    )
    (net (code "27") (name "Net-(PS1-C+)") (class "Default")
      (node (ref "C10") (pin "+") (pinfunction "+_+") (pintype "bidirectional"))
      (node (ref "PS1") (pin "P$3") (pinfunction "C+_P$3") (pintype "bidirectional"))
    )
    (net (code "28") (name "Net-(PS1-C-)") (class "Default")
      (node (ref "C10") (pin "-") (pinfunction "-_-") (pintype "bidirectional"))
      (node (ref "C13") (pin "P$1") (pinfunction "P$1_P$1") (pintype "bidirectional"))
      (node (ref "PS1") (pin "P$4") (pinfunction "C-_P$4") (pintype "bidirectional"))
    )
    (net (code "29") (name "Net-(PS1-VOUT)") (class "Default")
      (node (ref "C11") (pin "+") (pinfunction "+_+") (pintype "bidirectional"))
      (node (ref "L2") (pin "P$1") (pinfunction "P$1_P$1") (pintype "bidirectional"))
      (node (ref "PS1") (pin "P$6") (pinfunction "VOUT_P$6") (pintype "bidirectional"))
    )
    (net (code "30") (name "Net-(R17-P$3)") (class "Default")
      (node (ref "C14") (pin "P$2") (pinfunction "P$2_P$2") (pintype "bidirectional"))
      (node (ref "C15") (pin "P$2") (pinfunction "P$2_P$2") (pintype "bidirectional"))
      (node (ref "C16") (pin "P$2") (pinfunction "P$2_P$2") (pintype "bidirectional"))
      (node (ref "L3") (pin "P$1") (pinfunction "P$1_P$1") (pintype "bidirectional"))
      (node (ref "R17") (pin "P$1") (pinfunction "P$3_P$1") (pintype "bidirectional"))
    )
    (net (code "31") (name "Net-(R17-P$4)") (class "Default")
      (node (ref "F1") (pin "P$3") (pinfunction "P$2_P$3") (pintype "bidirectional"))
      (node (ref "F1") (pin "P$4") (pinfunction "P$2_P$4") (pintype "bidirectional"))
      (node (ref "R17") (pin "P$2") (pinfunction "P$4_P$2") (pintype "bidirectional"))
    )
    (net (code "32") (name "Net-(RP2040-4)") (class "Default")
      (node (ref "R9") (pin "P$1") (pinfunction "P$1_P$1") (pintype "bidirectional"))
      (node (ref "RP2040") (pin "P$4") (pinfunction "4_P$4") (pintype "bidirectional"))
    )
    (net (code "33") (name "Net-(RP2040-5)") (class "Default")
      (node (ref "R8") (pin "P$1") (pinfunction "P$1_P$1") (pintype "bidirectional"))
      (node (ref "RP2040") (pin "P$5") (pinfunction "5_P$5") (pintype "bidirectional"))
    )
    (net (code "34") (name "Net-(U1-EN)") (class "Default")
      (node (ref "R1") (pin "P$1") (pinfunction "P$1_P$1") (pintype "bidirectional"))
      (node (ref "R2") (pin "P$2") (pinfunction "P$2_P$2") (pintype "bidirectional"))
      (node (ref "U1") (pin "P$5") (pinfunction "EN_P$5") (pintype "bidirectional"))
    )
    (net (code "35") (name "Net-(U1-FB)") (class "Default")
      (node (ref "C9") (pin "P$1") (pinfunction "P$1_P$1") (pintype "bidirectional"))
      (node (ref "R3") (pin "P$1") (pinfunction "P$1_P$1") (pintype "bidirectional"))
      (node (ref "R4") (pin "P$1") (pinfunction "P$1_P$1") (pintype "bidirectional"))
      (node (ref "U1") (pin "P$6") (pinfunction "FB_P$6") (pintype "bidirectional"))
    )
    (net (code "36") (name "Net-(U1-SW)") (class "Default")
      (node (ref "L1") (pin "P$1") (pinfunction "P$1_P$1") (pintype "bidirectional"))
      (node (ref "U1") (pin "P$2") (pinfunction "SW_P$2") (pintype "bidirectional"))
    )
    (net (code "37") (name "Net-(U2-OUT)") (class "Default")
      (node (ref "R5") (pin "P$1") (pinfunction "P$1_P$1") (pintype "bidirectional"))
      (node (ref "U2") (pin "P$5") (pinfunction "OUT_P$5") (pintype "bidirectional"))
    )
    (net (code "38") (name "Net-(U3-OUT)") (class "Default")
      (node (ref "R6") (pin "P$1") (pinfunction "P$1_P$1") (pintype "bidirectional"))
      (node (ref "U3") (pin "P$5") (pinfunction "OUT_P$5") (pintype "bidirectional"))
    )
    (net (code "39") (name "Net-(U4-OUT)") (class "Default")
      (node (ref "R7") (pin "P$1") (pinfunction "P$1_P$1") (pintype "bidirectional"))
      (node (ref "U4") (pin "P$5") (pinfunction "OUT_P$5") (pintype "bidirectional"))
    )
    (net (code "40") (name "Net-(U5-A0)") (class "Default")
      (node (ref "A0H") (pin "P$1") (pinfunction "P$1_P$1") (pintype "bidirectional"))
      (node (ref "A0L") (pin "P$2") (pinfunction "P$2_P$2") (pintype "bidirectional"))
      (node (ref "U5") (pin "P$6") (pinfunction "A0_P$6") (pintype "bidirectional"))
    )
    (net (code "41") (name "Net-(U5-A1)") (class "Default")
      (node (ref "A1H") (pin "P$1") (pinfunction "P$1_P$1") (pintype "bidirectional"))
      (node (ref "A1L") (pin "P$2") (pinfunction "P$2_P$2") (pintype "bidirectional"))
      (node (ref "U5") (pin "P$7") (pinfunction "A1_P$7") (pintype "bidirectional"))
    )
    (net (code "42") (name "Net-(U5-A2)") (class "Default")
      (node (ref "A2H") (pin "P$1") (pinfunction "P$1_P$1") (pintype "bidirectional"))
      (node (ref "A2L") (pin "P$2") (pinfunction "P$2_P$2") (pintype "bidirectional"))
      (node (ref "U5") (pin "P$8") (pinfunction "A2_P$8") (pintype "bidirectional"))
    )
    (net (code "43") (name "Net-(U5-A3)") (class "Default")
      (node (ref "A3H") (pin "P$1") (pinfunction "P$1_P$1") (pintype "bidirectional"))
      (node (ref "A3L") (pin "P$2") (pinfunction "P$2_P$2") (pintype "bidirectional"))
      (node (ref "U5") (pin "P$9") (pinfunction "A3_P$9") (pintype "bidirectional"))
    )
    (net (code "44") (name "Net-(U5-VDD)") (class "Default")
      (node (ref "C33") (pin "P$2") (pinfunction "P$2_P$2") (pintype "bidirectional"))
      (node (ref "C34") (pin "P$2") (pinfunction "P$2_P$2") (pintype "bidirectional"))
      (node (ref "U5") (pin "P$4") (pinfunction "VDD_P$4") (pintype "bidirectional"))
      (node (ref "VR1") (pin "P$5") (pinfunction "VOUT_P$5") (pintype "bidirectional"))
    )
    (net (code "45") (name "Net-(U6-A0)") (class "Default")
      (node (ref "A0H1") (pin "P$1") (pinfunction "P$1_P$1") (pintype "bidirectional"))
      (node (ref "A0L1") (pin "P$2") (pinfunction "P$2_P$2") (pintype "bidirectional"))
      (node (ref "U6") (pin "P$6") (pinfunction "A0_P$6") (pintype "bidirectional"))
    )
    (net (code "46") (name "Net-(U6-A1)") (class "Default")
      (node (ref "A1H1") (pin "P$1") (pinfunction "P$1_P$1") (pintype "bidirectional"))
      (node (ref "A1L1") (pin "P$2") (pinfunction "P$2_P$2") (pintype "bidirectional"))
      (node (ref "U6") (pin "P$7") (pinfunction "A1_P$7") (pintype "bidirectional"))
    )
    (net (code "47") (name "Net-(U6-A2)") (class "Default")
      (node (ref "A2H1") (pin "P$1") (pinfunction "P$1_P$1") (pintype "bidirectional"))
      (node (ref "A2L1") (pin "P$2") (pinfunction "P$2_P$2") (pintype "bidirectional"))
      (node (ref "U6") (pin "P$8") (pinfunction "A2_P$8") (pintype "bidirectional"))
    )
    (net (code "48") (name "Net-(U6-A3)") (class "Default")
      (node (ref "A3H1") (pin "P$1") (pinfunction "P$1_P$1") (pintype "bidirectional"))
      (node (ref "A3L1") (pin "P$2") (pinfunction "P$2_P$2") (pintype "bidirectional"))
      (node (ref "U6") (pin "P$9") (pinfunction "A3_P$9") (pintype "bidirectional"))
    )
    (net (code "49") (name "Net-(U6-VDD)") (class "Default")
      (node (ref "C37") (pin "P$2") (pinfunction "P$2_P$2") (pintype "bidirectional"))
      (node (ref "C38") (pin "P$2") (pinfunction "P$2_P$2") (pintype "bidirectional"))
      (node (ref "U6") (pin "P$4") (pinfunction "VDD_P$4") (pintype "bidirectional"))
      (node (ref "VR2") (pin "P$5") (pinfunction "VOUT_P$5") (pintype "bidirectional"))
    )
    (net (code "50") (name "Net-(U7-A0)") (class "Default")
      (node (ref "A0H2") (pin "P$1") (pinfunction "P$1_P$1") (pintype "bidirectional"))
      (node (ref "A0L2") (pin "P$2") (pinfunction "P$2_P$2") (pintype "bidirectional"))
      (node (ref "U7") (pin "P$6") (pinfunction "A0_P$6") (pintype "bidirectional"))
    )
    (net (code "51") (name "Net-(U7-A1)") (class "Default")
      (node (ref "A1H2") (pin "P$1") (pinfunction "P$1_P$1") (pintype "bidirectional"))
      (node (ref "A1L2") (pin "P$2") (pinfunction "P$2_P$2") (pintype "bidirectional"))
      (node (ref "U7") (pin "P$7") (pinfunction "A1_P$7") (pintype "bidirectional"))
    )
    (net (code "52") (name "Net-(U7-A2)") (class "Default")
      (node (ref "A2H2") (pin "P$1") (pinfunction "P$1_P$1") (pintype "bidirectional"))
      (node (ref "A2L2") (pin "P$2") (pinfunction "P$2_P$2") (pintype "bidirectional"))
      (node (ref "U7") (pin "P$8") (pinfunction "A2_P$8") (pintype "bidirectional"))
    )
    (net (code "53") (name "Net-(U7-A3)") (class "Default")
      (node (ref "A3H2") (pin "P$1") (pinfunction "P$1_P$1") (pintype "bidirectional"))
      (node (ref "A3L2") (pin "P$2") (pinfunction "P$2_P$2") (pintype "bidirectional"))
      (node (ref "U7") (pin "P$9") (pinfunction "A3_P$9") (pintype "bidirectional"))
    )
    (net (code "54") (name "Net-(U7-VDD)") (class "Default")
      (node (ref "C41") (pin "P$2") (pinfunction "P$2_P$2") (pintype "bidirectional"))
      (node (ref "C42") (pin "P$2") (pinfunction "P$2_P$2") (pintype "bidirectional"))
      (node (ref "U7") (pin "P$4") (pinfunction "VDD_P$4") (pintype "bidirectional"))
      (node (ref "VR3") (pin "P$5") (pinfunction "VOUT_P$5") (pintype "bidirectional"))
    )
    (net (code "55") (name "SPI_CLK") (class "Default")
      (node (ref "DISP1") (pin "P$17") (pinfunction "CLK_P$17") (pintype "bidirectional"))
      (node (ref "RP2040") (pin "P$24") (pinfunction "24_P$24") (pintype "bidirectional"))
    )
    (net (code "56") (name "SPI_CS") (class "Default")
      (node (ref "DISP1") (pin "P$14") (pinfunction "CS_P$14") (pintype "bidirectional"))
      (node (ref "RP2040") (pin "P$22") (pinfunction "22_P$22") (pintype "bidirectional"))
    )
    (net (code "57") (name "SPI_DS") (class "Default")
      (node (ref "DISP1") (pin "P$13") (pinfunction "D/C_P$13") (pintype "bidirectional"))
      (node (ref "DISP1") (pin "P$9") (pinfunction "X+_P$9") (pintype "bidirectional"))
      (node (ref "RP2040") (pin "P$26") (pinfunction "26_P$26") (pintype "bidirectional"))
    )
    (net (code "58") (name "SPI_RX") (class "Default")
      (node (ref "DISP1") (pin "P$16") (pinfunction "MISO_P$16") (pintype "bidirectional"))
      (node (ref "RP2040") (pin "P$21") (pinfunction "21_P$21") (pintype "bidirectional"))
    )
    (net (code "59") (name "SPI_TX") (class "Default")
      (node (ref "DISP1") (pin "P$15") (pinfunction "MOSI_P$15") (pintype "bidirectional"))
      (node (ref "RP2040") (pin "P$25") (pinfunction "25_P$25") (pintype "bidirectional"))
    )
    (net (code "60") (name "T1+") (class "Default")
      (node (ref "C32") (pin "P$2") (pinfunction "P$2_P$2") (pintype "bidirectional"))
      (node (ref "H10") (pin "P$2") (pinfunction "2_P$2") (pintype "bidirectional"))
      (node (ref "U5") (pin "P$3") (pinfunction "T+_P$3") (pintype "bidirectional"))
    )
    (net (code "61") (name "T1-") (class "Default")
      (node (ref "C32") (pin "P$1") (pinfunction "P$1_P$1") (pintype "bidirectional"))
      (node (ref "H10") (pin "P$1") (pinfunction "1_P$1") (pintype "bidirectional"))
      (node (ref "U5") (pin "P$2") (pinfunction "T-_P$2") (pintype "bidirectional"))
    )
    (net (code "62") (name "T2+") (class "Default")
      (node (ref "C36") (pin "P$2") (pinfunction "P$2_P$2") (pintype "bidirectional"))
      (node (ref "H11") (pin "P$2") (pinfunction "2_P$2") (pintype "bidirectional"))
      (node (ref "U6") (pin "P$3") (pinfunction "T+_P$3") (pintype "bidirectional"))
    )
    (net (code "63") (name "T2-") (class "Default")
      (node (ref "C36") (pin "P$1") (pinfunction "P$1_P$1") (pintype "bidirectional"))
      (node (ref "H11") (pin "P$1") (pinfunction "1_P$1") (pintype "bidirectional"))
      (node (ref "U6") (pin "P$2") (pinfunction "T-_P$2") (pintype "bidirectional"))
    )
    (net (code "64") (name "T3+") (class "Default")
      (node (ref "C40") (pin "P$2") (pinfunction "P$2_P$2") (pintype "bidirectional"))
      (node (ref "H12") (pin "P$2") (pinfunction "2_P$2") (pintype "bidirectional"))
      (node (ref "U7") (pin "P$3") (pinfunction "T+_P$3") (pintype "bidirectional"))
    )
    (net (code "65") (name "T3-") (class "Default")
      (node (ref "C40") (pin "P$1") (pinfunction "P$1_P$1") (pintype "bidirectional"))
      (node (ref "H12") (pin "P$1") (pinfunction "1_P$1") (pintype "bidirectional"))
      (node (ref "U7") (pin "P$2") (pinfunction "T-_P$2") (pintype "bidirectional"))
    )
    (net (code "66") (name "X-") (class "Default")
      (node (ref "DISP1") (pin "P$7") (pinfunction "X-_P$7") (pintype "bidirectional"))
      (node (ref "RP2040") (pin "P$32") (pinfunction "32_P$32") (pintype "bidirectional"))
    )
    (net (code "67") (name "Y+") (class "Default")
      (node (ref "DISP1") (pin "P$10") (pinfunction "Y+_P$10") (pintype "bidirectional"))
      (node (ref "RP2040") (pin "P$31") (pinfunction "31_P$31") (pintype "bidirectional"))
    )
    (net (code "68") (name "Y-") (class "Default")
      (node (ref "DISP1") (pin "P$8") (pinfunction "Y-_P$8") (pintype "bidirectional"))
      (node (ref "RP2040") (pin "P$27") (pinfunction "27_P$27") (pintype "bidirectional"))
    )
    (net (code "69") (name "unconnected-(DISP1-3V3-PadP$18)") (class "Default")
      (node (ref "DISP1") (pin "P$18") (pinfunction "3V3_P$18") (pintype "bidirectional"))
    )
    (net (code "70") (name "unconnected-(DISP1-BK_LT-PadP$11)") (class "Default")
      (node (ref "DISP1") (pin "P$11") (pinfunction "BK_LT_P$11") (pintype "bidirectional"))
    )
    (net (code "71") (name "unconnected-(DISP1-CRD_CS-PadP$2)") (class "Default")
      (node (ref "DISP1") (pin "P$2") (pinfunction "CRD_CS_P$2") (pintype "bidirectional"))
    )
    (net (code "72") (name "unconnected-(DISP1-CRD_DET-PadP$1)") (class "Default")
      (node (ref "DISP1") (pin "P$1") (pinfunction "CRD_DET_P$1") (pintype "bidirectional"))
    )
    (net (code "73") (name "unconnected-(DISP1-C{slash}D-PadP$25)") (class "Default")
      (node (ref "DISP1") (pin "P$25") (pinfunction "C/D_P$25") (pintype "bidirectional"))
    )
    (net (code "74") (name "unconnected-(DISP1-D0-PadP$33)") (class "Default")
      (node (ref "DISP1") (pin "P$33") (pinfunction "D0_P$33") (pintype "bidirectional"))
    )
    (net (code "75") (name "unconnected-(DISP1-D1-PadP$34)") (class "Default")
      (node (ref "DISP1") (pin "P$34") (pinfunction "D1_P$34") (pintype "bidirectional"))
    )
    (net (code "76") (name "unconnected-(DISP1-D2-PadP$35)") (class "Default")
      (node (ref "DISP1") (pin "P$35") (pinfunction "D2_P$35") (pintype "bidirectional"))
    )
    (net (code "77") (name "unconnected-(DISP1-D3-PadP$36)") (class "Default")
      (node (ref "DISP1") (pin "P$36") (pinfunction "D3_P$36") (pintype "bidirectional"))
    )
    (net (code "78") (name "unconnected-(DISP1-D4-PadP$37)") (class "Default")
      (node (ref "DISP1") (pin "P$37") (pinfunction "D4_P$37") (pintype "bidirectional"))
    )
    (net (code "79") (name "unconnected-(DISP1-D5-PadP$38)") (class "Default")
      (node (ref "DISP1") (pin "P$38") (pinfunction "D5_P$38") (pintype "bidirectional"))
    )
    (net (code "80") (name "unconnected-(DISP1-D6-PadP$39)") (class "Default")
      (node (ref "DISP1") (pin "P$39") (pinfunction "D6_P$39") (pintype "bidirectional"))
    )
    (net (code "81") (name "unconnected-(DISP1-D7-PadP$40)") (class "Default")
      (node (ref "DISP1") (pin "P$40") (pinfunction "D7_P$40") (pintype "bidirectional"))
    )
    (net (code "82") (name "unconnected-(DISP1-IM0-PadP$3)") (class "Default")
      (node (ref "DISP1") (pin "P$3") (pinfunction "IM0_P$3") (pintype "bidirectional"))
    )
    (net (code "83") (name "unconnected-(DISP1-IM1-PadP$4)") (class "Default")
      (node (ref "DISP1") (pin "P$4") (pinfunction "IM1_P$4") (pintype "bidirectional"))
    )
    (net (code "84") (name "unconnected-(DISP1-IM2-PadP$5)") (class "Default")
      (node (ref "DISP1") (pin "P$5") (pinfunction "IM2_P$5") (pintype "bidirectional"))
    )
    (net (code "85") (name "unconnected-(DISP1-IM3-PadP$6)") (class "Default")
      (node (ref "DISP1") (pin "P$6") (pinfunction "IM3_P$6") (pintype "bidirectional"))
    )
    (net (code "86") (name "unconnected-(DISP1-NC$1-PadP$32)") (class "Default")
      (node (ref "DISP1") (pin "P$32") (pinfunction "NC$1_P$32") (pintype "bidirectional"))
    )
    (net (code "87") (name "unconnected-(DISP1-NC$2-PadP$31)") (class "Default")
      (node (ref "DISP1") (pin "P$31") (pinfunction "NC$2_P$31") (pintype "bidirectional"))
    )
    (net (code "88") (name "unconnected-(DISP1-NC$3-PadP$30)") (class "Default")
      (node (ref "DISP1") (pin "P$30") (pinfunction "NC$3_P$30") (pintype "bidirectional"))
    )
    (net (code "89") (name "unconnected-(DISP1-NC$4-PadP$29)") (class "Default")
      (node (ref "DISP1") (pin "P$29") (pinfunction "NC$4_P$29") (pintype "bidirectional"))
    )
    (net (code "90") (name "unconnected-(DISP1-NC$5-PadP$28)") (class "Default")
      (node (ref "DISP1") (pin "P$28") (pinfunction "NC$5_P$28") (pintype "bidirectional"))
    )
    (net (code "91") (name "unconnected-(DISP1-NC$6-PadP$24)") (class "Default")
      (node (ref "DISP1") (pin "P$24") (pinfunction "NC$6_P$24") (pintype "bidirectional"))
    )
    (net (code "92") (name "unconnected-(DISP1-NC$7-PadP$23)") (class "Default")
      (node (ref "DISP1") (pin "P$23") (pinfunction "NC$7_P$23") (pintype "bidirectional"))
    )
    (net (code "93") (name "unconnected-(DISP1-NC$8-PadP$22)") (class "Default")
      (node (ref "DISP1") (pin "P$22") (pinfunction "NC$8_P$22") (pintype "bidirectional"))
    )
    (net (code "94") (name "unconnected-(DISP1-NC$9-PadP$21)") (class "Default")
      (node (ref "DISP1") (pin "P$21") (pinfunction "NC$9_P$21") (pintype "bidirectional"))
    )
    (net (code "95") (name "unconnected-(DISP1-RD-PadP$27)") (class "Default")
      (node (ref "DISP1") (pin "P$27") (pinfunction "RD_P$27") (pintype "bidirectional"))
    )
    (net (code "96") (name "unconnected-(DISP1-RST-PadP$12)") (class "Default")
      (node (ref "DISP1") (pin "P$12") (pinfunction "RST_P$12") (pintype "bidirectional"))
    )
    (net (code "97") (name "unconnected-(DISP1-WR-PadP$26)") (class "Default")
      (node (ref "DISP1") (pin "P$26") (pinfunction "WR_P$26") (pintype "bidirectional"))
    )
    (net (code "98") (name "unconnected-(RP2040-1-PadP$1)") (class "Default")
      (node (ref "RP2040") (pin "P$1") (pinfunction "1_P$1") (pintype "bidirectional"))
    )
    (net (code "99") (name "unconnected-(RP2040-2-PadP$2)") (class "Default")
      (node (ref "RP2040") (pin "P$2") (pinfunction "2_P$2") (pintype "bidirectional"))
    )
    (net (code "100") (name "unconnected-(RP2040-3V3_EN-PadP$37)") (class "Default")
      (node (ref "RP2040") (pin "P$37") (pinfunction "3V3_EN_P$37") (pintype "bidirectional"))
    )
    (net (code "101") (name "unconnected-(RP2040-17-PadP$17)") (class "Default")
      (node (ref "RP2040") (pin "P$17") (pinfunction "17_P$17") (pintype "bidirectional"))
    )
    (net (code "102") (name "unconnected-(RP2040-19-PadP$19)") (class "Default")
      (node (ref "RP2040") (pin "P$19") (pinfunction "19_P$19") (pintype "bidirectional"))
    )
    (net (code "103") (name "unconnected-(RP2040-20-PadP$20)") (class "Default")
      (node (ref "RP2040") (pin "P$20") (pinfunction "20_P$20") (pintype "bidirectional"))
    )
    (net (code "104") (name "unconnected-(RP2040-34-PadP$34)") (class "Default")
      (node (ref "RP2040") (pin "P$34") (pinfunction "34_P$34") (pintype "bidirectional"))
    )
    (net (code "105") (name "unconnected-(RP2040-RUN-PadP$30)") (class "Default")
      (node (ref "RP2040") (pin "P$30") (pinfunction "RUN_P$30") (pintype "bidirectional"))
    )
    (net (code "106") (name "unconnected-(RP2040-VBUS-PadP$40)") (class "Default")
      (node (ref "RP2040") (pin "P$40") (pinfunction "VBUS_P$40") (pintype "bidirectional"))
    )
    (net (code "107") (name "unconnected-(RP2040-VREF-PadP$35)") (class "Default")
      (node (ref "RP2040") (pin "P$35") (pinfunction "VREF_P$35") (pintype "bidirectional"))
    )
  )
)
